# WimarcFarmArduinoShield.net
KiCad netlist of a schematic drawn in EAGLE
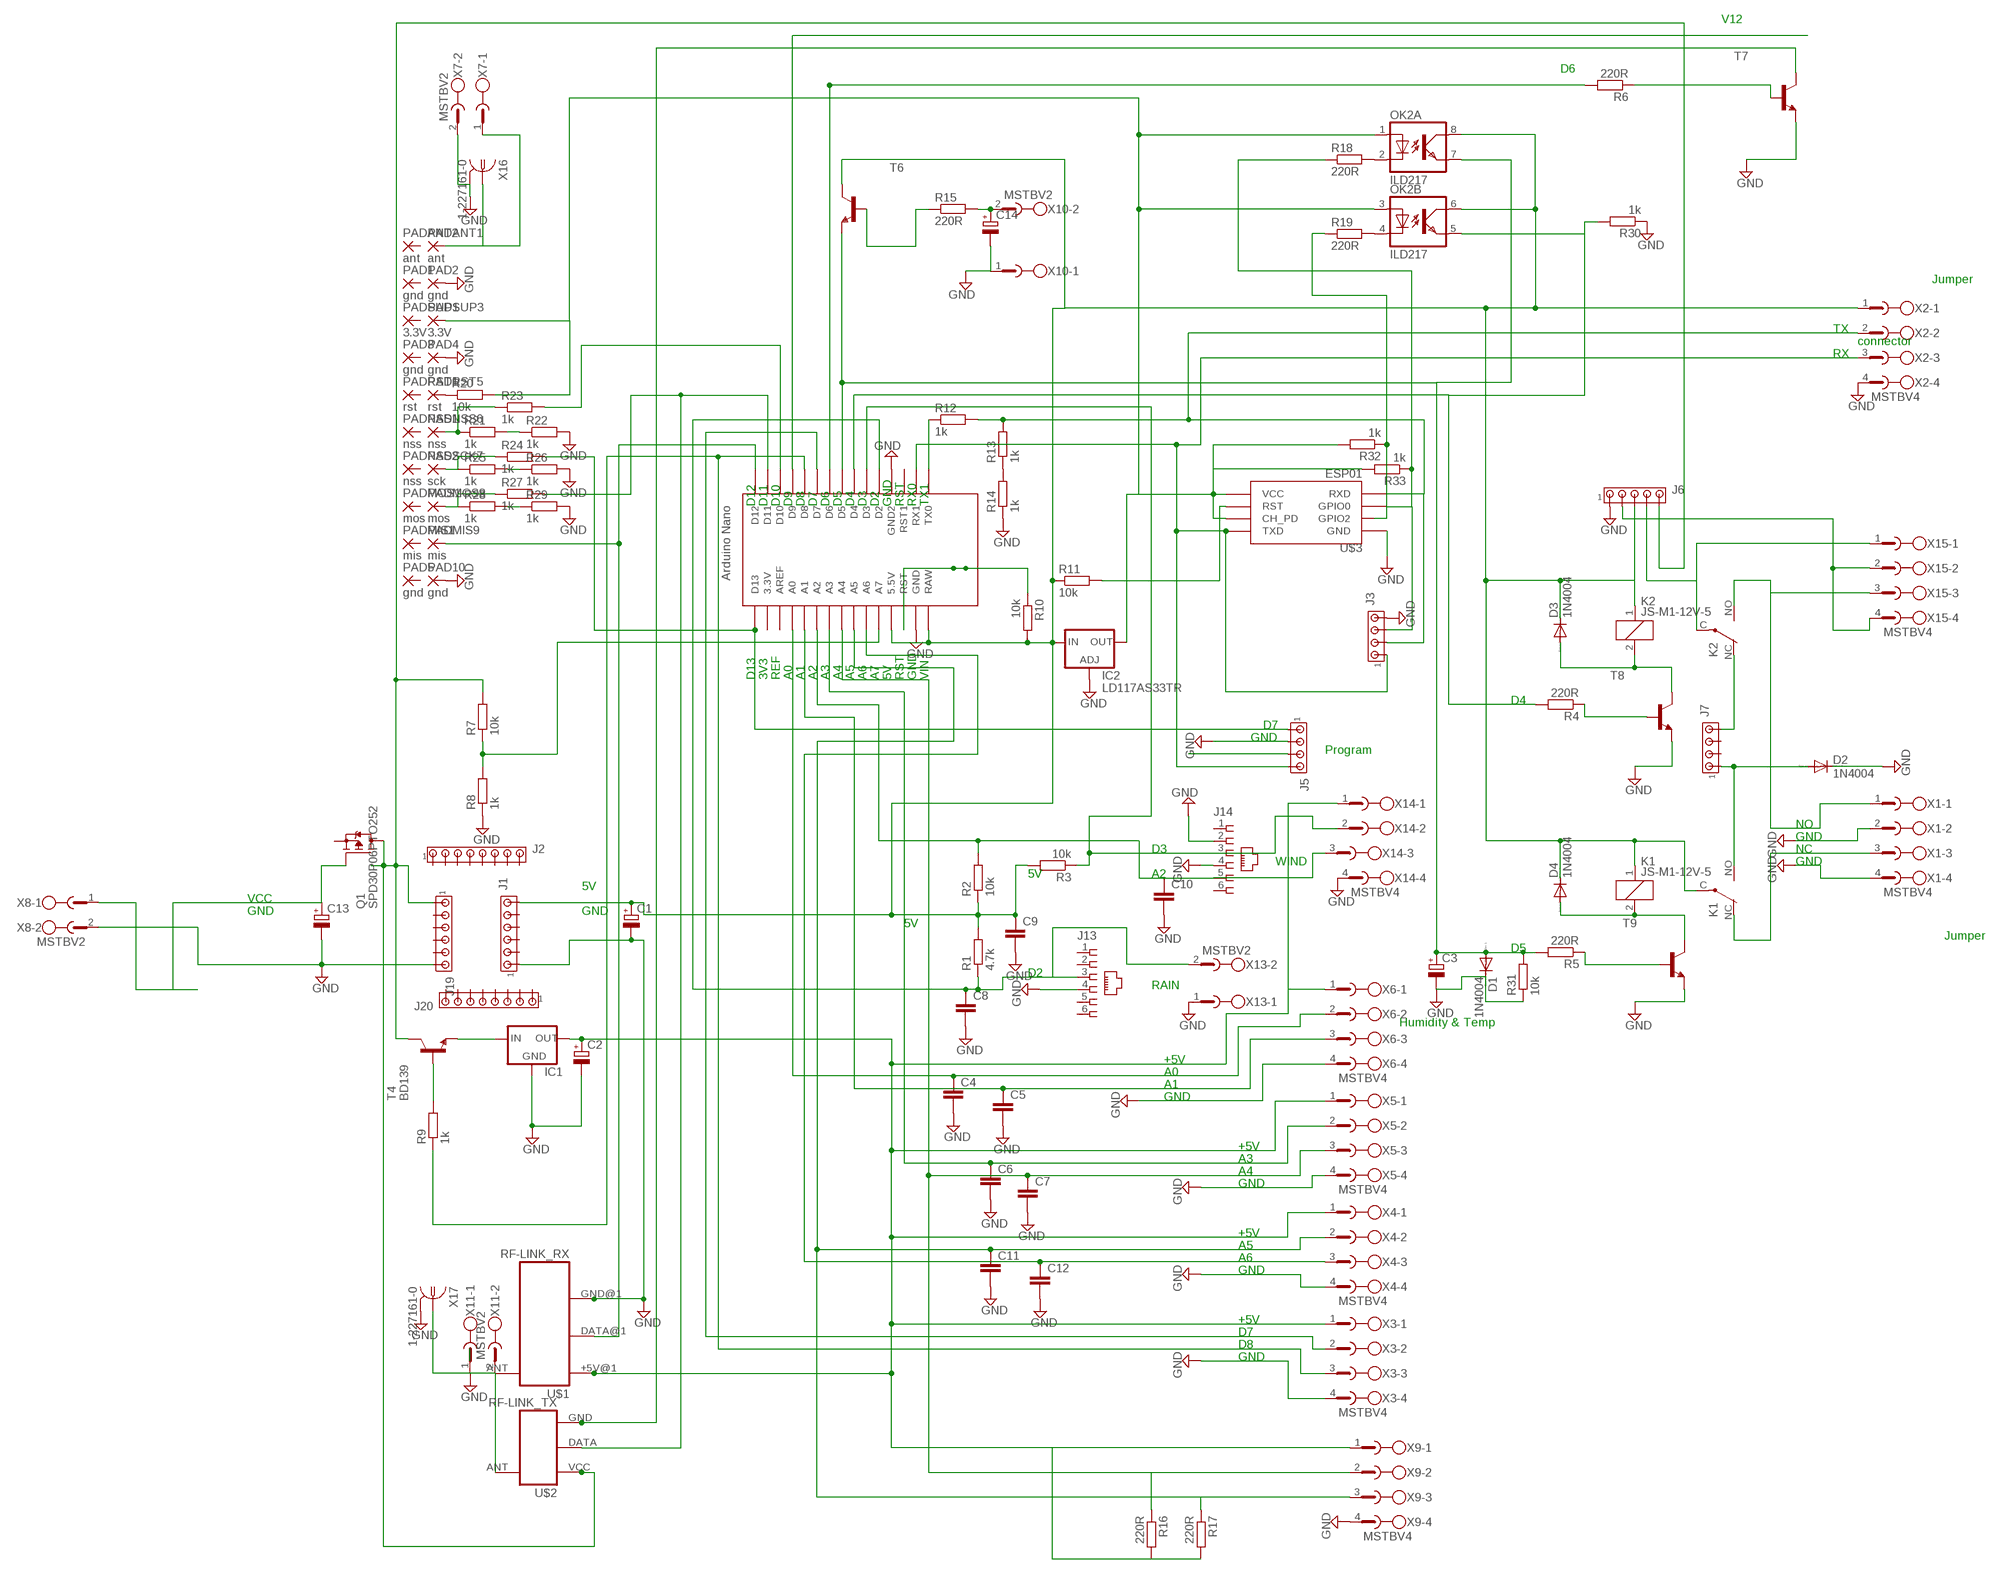
[diagram p0: schematic, sheet 1]

(export (version "E")
  (design (tool "Eeschema 10.0.6"))
  (components
    (comp (ref "C1")
      (value "CPOL-EUE2.5-7")
      (footprint "eagle-import:E2,5-7")
      (libsource (lib "eagle-import") (part "CPOL-EUE2.5-7"))
    )
    (comp (ref "C2")
      (value "CPOL-EUE3.5-10")
      (footprint "eagle-import:E3,5-10")
      (libsource (lib "eagle-import") (part "CPOL-EUE3.5-10"))
    )
    (comp (ref "C3")
      (value "CPOL-EUE2.5-7")
      (footprint "eagle-import:E2,5-7")
      (libsource (lib "eagle-import") (part "CPOL-EUE2.5-7"))
    )
    (comp (ref "C4")
      (value "C-EUC0805K")
      (footprint "eagle-import:C0805K")
      (libsource (lib "eagle-import") (part "C-EUC0805K"))
    )
    (comp (ref "C5")
      (value "C-EUC0805K")
      (footprint "eagle-import:C0805K")
      (libsource (lib "eagle-import") (part "C-EUC0805K"))
    )
    (comp (ref "C6")
      (value "C-EUC0805K")
      (footprint "eagle-import:C0805K")
      (libsource (lib "eagle-import") (part "C-EUC0805K"))
    )
    (comp (ref "C7")
      (value "C-EUC0805K")
      (footprint "eagle-import:C0805K")
      (libsource (lib "eagle-import") (part "C-EUC0805K"))
    )
    (comp (ref "C8")
      (value "C-EUC0805K")
      (footprint "eagle-import:C0805K")
      (libsource (lib "eagle-import") (part "C-EUC0805K"))
    )
    (comp (ref "C9")
      (value "C-EUC0805K")
      (footprint "eagle-import:C0805K")
      (libsource (lib "eagle-import") (part "C-EUC0805K"))
    )
    (comp (ref "C10")
      (value "C-EUC0805K")
      (footprint "eagle-import:C0805K")
      (libsource (lib "eagle-import") (part "C-EUC0805K"))
    )
    (comp (ref "C11")
      (value "C-EUC0805K")
      (footprint "eagle-import:C0805K")
      (libsource (lib "eagle-import") (part "C-EUC0805K"))
    )
    (comp (ref "C12")
      (value "C-EUC0805K")
      (footprint "eagle-import:C0805K")
      (libsource (lib "eagle-import") (part "C-EUC0805K"))
    )
    (comp (ref "C13")
      (value "CPOL-EUE2.5-7")
      (footprint "eagle-import:E2,5-7")
      (libsource (lib "eagle-import") (part "CPOL-EUE2.5-7"))
    )
    (comp (ref "C14")
      (value "CPOL-EUE2.5-7")
      (footprint "eagle-import:E2,5-7")
      (libsource (lib "eagle-import") (part "CPOL-EUE2.5-7"))
    )
    (comp (ref "D1")
      (value "1N4004")
      (footprint "eagle-import:DO41-10")
      (libsource (lib "eagle-import") (part "1N4004"))
    )
    (comp (ref "D2")
      (value "1N4004")
      (footprint "eagle-import:DO41-10")
      (libsource (lib "eagle-import") (part "1N4004"))
    )
    (comp (ref "D3")
      (value "1N4004")
      (footprint "eagle-import:DO41-10")
      (libsource (lib "eagle-import") (part "1N4004"))
    )
    (comp (ref "D4")
      (value "1N4004")
      (footprint "eagle-import:DO41-10")
      (libsource (lib "eagle-import") (part "1N4004"))
    )
    (comp (ref "IC1")
      (value "78XXS")
      (footprint "eagle-import:78XXS")
      (libsource (lib "eagle-import") (part "78XXS"))
    )
    (comp (ref "IC2")
      (value "LD117AS33TR")
      (footprint "eagle-import:SOT223")
      (libsource (lib "eagle-import") (part "LD117A?S33TR"))
    )
    (comp (ref "J1")
      (value "MTA06-100")
      (footprint "eagle-import:10X06MTA")
      (libsource (lib "eagle-import") (part "MTA06-100"))
    )
    (comp (ref "J2")
      (value "MTA08-100")
      (footprint "eagle-import:10X08MTA")
      (libsource (lib "eagle-import") (part "MTA08-100"))
    )
    (comp (ref "J3")
      (value "MTA04-100")
      (footprint "eagle-import:10X04MTA")
      (libsource (lib "eagle-import") (part "MTA04-100"))
    )
    (comp (ref "J5")
      (value "MTA04-100")
      (footprint "eagle-import:10X04MTA")
      (libsource (lib "eagle-import") (part "MTA04-100"))
    )
    (comp (ref "J6")
      (value "MTA05-100")
      (footprint "eagle-import:10X05MTA")
      (libsource (lib "eagle-import") (part "MTA05-100"))
    )
    (comp (ref "J7")
      (value "MTA04-100")
      (footprint "eagle-import:10X04MTA")
      (libsource (lib "eagle-import") (part "MTA04-100"))
    )
    (comp (ref "J13")
      (value "520250-3")
      (footprint "eagle-import:520250-3")
      (libsource (lib "eagle-import") (part "520250-3"))
    )
    (comp (ref "J14")
      (value "520250-3")
      (footprint "eagle-import:520250-3")
      (libsource (lib "eagle-import") (part "520250-3"))
    )
    (comp (ref "J19")
      (value "MTA06-100")
      (footprint "eagle-import:10X06MTA")
      (libsource (lib "eagle-import") (part "MTA06-100"))
    )
    (comp (ref "J20")
      (value "MTA08-100")
      (footprint "eagle-import:10X08MTA")
      (libsource (lib "eagle-import") (part "MTA08-100"))
    )
    (comp (ref "K1")
      (value "JS-M1-12V-5")
      (footprint "eagle-import:JS-M")
      (libsource (lib "eagle-import") (part "JS-M1-12V-5"))
    )
    (comp (ref "K2")
      (value "JS-M1-12V-5")
      (footprint "eagle-import:JS-M")
      (libsource (lib "eagle-import") (part "JS-M1-12V-5"))
    )
    (comp (ref "OK2")
      (value "ILD217")
      (footprint "eagle-import:SOIC08")
      (libsource (lib "eagle-import") (part "ILD217"))
    )
    (comp (ref "PAD1")
      (value "gnd")
      (footprint "eagle-import:1,6_0,8")
      (libsource (lib "eagle-import") (part "1,6/0,8"))
    )
    (comp (ref "PAD2")
      (value "gnd")
      (footprint "eagle-import:1,6_0,8")
      (libsource (lib "eagle-import") (part "1,6/0,8"))
    )
    (comp (ref "PAD3")
      (value "gnd")
      (footprint "eagle-import:1,6_0,8")
      (libsource (lib "eagle-import") (part "1,6/0,8"))
    )
    (comp (ref "PAD4")
      (value "gnd")
      (footprint "eagle-import:1,6_0,8")
      (libsource (lib "eagle-import") (part "1,6/0,8"))
    )
    (comp (ref "PAD5")
      (value "gnd")
      (footprint "eagle-import:1,6_0,8")
      (libsource (lib "eagle-import") (part "1,6/0,8"))
    )
    (comp (ref "PAD10")
      (value "gnd")
      (footprint "eagle-import:1,6_0,8")
      (libsource (lib "eagle-import") (part "1,6/0,8"))
    )
    (comp (ref "PADANT1")
      (value "ant")
      (footprint "eagle-import:1,6_0,8")
      (libsource (lib "eagle-import") (part "1,6/0,8"))
    )
    (comp (ref "PADANT2")
      (value "ant")
      (footprint "eagle-import:1,6_0,8")
      (libsource (lib "eagle-import") (part "1,6/0,8"))
    )
    (comp (ref "PADMIS1")
      (value "mis")
      (footprint "eagle-import:1,6_0,8")
      (libsource (lib "eagle-import") (part "1,6/0,8"))
    )
    (comp (ref "PADMIS9")
      (value "mis")
      (footprint "eagle-import:1,6_0,8")
      (libsource (lib "eagle-import") (part "1,6/0,8"))
    )
    (comp (ref "PADMOS1")
      (value "mos")
      (footprint "eagle-import:1,6_0,8")
      (libsource (lib "eagle-import") (part "1,6/0,8"))
    )
    (comp (ref "PADMOS8")
      (value "mos")
      (footprint "eagle-import:1,6_0,8")
      (libsource (lib "eagle-import") (part "1,6/0,8"))
    )
    (comp (ref "PADNSS1")
      (value "nss")
      (footprint "eagle-import:1,6_0,8")
      (libsource (lib "eagle-import") (part "1,6/0,8"))
    )
    (comp (ref "PADNSS2")
      (value "nss")
      (footprint "eagle-import:1,6_0,8")
      (libsource (lib "eagle-import") (part "1,6/0,8"))
    )
    (comp (ref "PADNSS6")
      (value "nss")
      (footprint "eagle-import:1,6_0,8")
      (libsource (lib "eagle-import") (part "1,6/0,8"))
    )
    (comp (ref "PADRST1")
      (value "rst")
      (footprint "eagle-import:1,6_0,8")
      (libsource (lib "eagle-import") (part "1,6/0,8"))
    )
    (comp (ref "PADRST5")
      (value "rst")
      (footprint "eagle-import:1,6_0,8")
      (libsource (lib "eagle-import") (part "1,6/0,8"))
    )
    (comp (ref "PADSCK7")
      (value "sck")
      (footprint "eagle-import:1,6_0,8")
      (libsource (lib "eagle-import") (part "1,6/0,8"))
    )
    (comp (ref "PADSUP1")
      (value "3.3V")
      (footprint "eagle-import:1,6_0,8")
      (libsource (lib "eagle-import") (part "1,6/0,8"))
    )
    (comp (ref "PADSUP3")
      (value "3.3V")
      (footprint "eagle-import:1,6_0,8")
      (libsource (lib "eagle-import") (part "1,6/0,8"))
    )
    (comp (ref "Q1")
      (value "SPD30P06PTO252")
      (footprint "eagle-import:TO252")
      (libsource (lib "eagle-import") (part "SPD30P06PTO252"))
    )
    (comp (ref "R1")
      (value "4.7k")
      (footprint "eagle-import:M0805")
      (libsource (lib "eagle-import") (part "R-EU_M0805"))
    )
    (comp (ref "R2")
      (value "10k")
      (footprint "eagle-import:M0805")
      (libsource (lib "eagle-import") (part "R-EU_M0805"))
    )
    (comp (ref "R3")
      (value "10k")
      (footprint "eagle-import:M0805")
      (libsource (lib "eagle-import") (part "R-EU_M0805"))
    )
    (comp (ref "R4")
      (value "220R")
      (footprint "eagle-import:M0805")
      (libsource (lib "eagle-import") (part "R-EU_M0805"))
    )
    (comp (ref "R5")
      (value "220R")
      (footprint "eagle-import:M0805")
      (libsource (lib "eagle-import") (part "R-EU_M0805"))
    )
    (comp (ref "R6")
      (value "220R")
      (footprint "eagle-import:M0805")
      (libsource (lib "eagle-import") (part "R-EU_M0805"))
    )
    (comp (ref "R7")
      (value "10k")
      (footprint "eagle-import:M0805")
      (libsource (lib "eagle-import") (part "R-EU_M0805"))
    )
    (comp (ref "R8")
      (value "1k")
      (footprint "eagle-import:M0805")
      (libsource (lib "eagle-import") (part "R-EU_M0805"))
    )
    (comp (ref "R9")
      (value "1k")
      (footprint "eagle-import:M0805")
      (libsource (lib "eagle-import") (part "R-EU_M0805"))
    )
    (comp (ref "R10")
      (value "10k")
      (footprint "eagle-import:M0805")
      (libsource (lib "eagle-import") (part "R-EU_M0805"))
    )
    (comp (ref "R11")
      (value "10k")
      (footprint "eagle-import:M0805")
      (libsource (lib "eagle-import") (part "R-EU_M0805"))
    )
    (comp (ref "R12")
      (value "1k")
      (footprint "eagle-import:M0805")
      (libsource (lib "eagle-import") (part "R-EU_M0805"))
    )
    (comp (ref "R13")
      (value "1k")
      (footprint "eagle-import:M0805")
      (libsource (lib "eagle-import") (part "R-EU_M0805"))
    )
    (comp (ref "R14")
      (value "1k")
      (footprint "eagle-import:M0805")
      (libsource (lib "eagle-import") (part "R-EU_M0805"))
    )
    (comp (ref "R15")
      (value "220R")
      (footprint "eagle-import:M0805")
      (libsource (lib "eagle-import") (part "R-EU_M0805"))
    )
    (comp (ref "R16")
      (value "220R")
      (footprint "eagle-import:M0805")
      (libsource (lib "eagle-import") (part "R-EU_M0805"))
    )
    (comp (ref "R17")
      (value "220R")
      (footprint "eagle-import:M0805")
      (libsource (lib "eagle-import") (part "R-EU_M0805"))
    )
    (comp (ref "R18")
      (value "220R")
      (footprint "eagle-import:M0805")
      (libsource (lib "eagle-import") (part "R-EU_M0805"))
    )
    (comp (ref "R19")
      (value "220R")
      (footprint "eagle-import:M0805")
      (libsource (lib "eagle-import") (part "R-EU_M0805"))
    )
    (comp (ref "R20")
      (value "10k")
      (footprint "eagle-import:M0805")
      (libsource (lib "eagle-import") (part "R-EU_M0805"))
    )
    (comp (ref "R21")
      (value "1k")
      (footprint "eagle-import:M0805")
      (libsource (lib "eagle-import") (part "R-EU_M0805"))
    )
    (comp (ref "R22")
      (value "1k")
      (footprint "eagle-import:M0805")
      (libsource (lib "eagle-import") (part "R-EU_M0805"))
    )
    (comp (ref "R23")
      (value "1k")
      (footprint "eagle-import:M0805")
      (libsource (lib "eagle-import") (part "R-EU_M0805"))
    )
    (comp (ref "R24")
      (value "1k")
      (footprint "eagle-import:M0805")
      (libsource (lib "eagle-import") (part "R-EU_M0805"))
    )
    (comp (ref "R25")
      (value "1k")
      (footprint "eagle-import:M0805")
      (libsource (lib "eagle-import") (part "R-EU_M0805"))
    )
    (comp (ref "R26")
      (value "1k")
      (footprint "eagle-import:M0805")
      (libsource (lib "eagle-import") (part "R-EU_M0805"))
    )
    (comp (ref "R27")
      (value "1k")
      (footprint "eagle-import:M0805")
      (libsource (lib "eagle-import") (part "R-EU_M0805"))
    )
    (comp (ref "R28")
      (value "1k")
      (footprint "eagle-import:M0805")
      (libsource (lib "eagle-import") (part "R-EU_M0805"))
    )
    (comp (ref "R29")
      (value "1k")
      (footprint "eagle-import:M0805")
      (libsource (lib "eagle-import") (part "R-EU_M0805"))
    )
    (comp (ref "R30")
      (value "1k")
      (footprint "eagle-import:M0805")
      (libsource (lib "eagle-import") (part "R-EU_M0805"))
    )
    (comp (ref "R31")
      (value "10k")
      (footprint "eagle-import:M0805")
      (libsource (lib "eagle-import") (part "R-EU_M0805"))
    )
    (comp (ref "R32")
      (value "1k")
      (footprint "eagle-import:M0805")
      (libsource (lib "eagle-import") (part "R-EU_M0805"))
    )
    (comp (ref "R33")
      (value "1k")
      (footprint "eagle-import:M0805")
      (libsource (lib "eagle-import") (part "R-EU_M0805"))
    )
    (comp (ref "T4")
      (value "BD139")
      (footprint "eagle-import:TO126")
      (libsource (lib "eagle-import") (part "BD139"))
    )
    (comp (ref "T6")
      (value "-NPN-SOT89-BCE")
      (footprint "eagle-import:SOT89-BCE")
      (libsource (lib "eagle-import") (part "-NPN-SOT89-BCE"))
    )
    (comp (ref "T7")
      (value "-NPN-SOT89-BCE")
      (footprint "eagle-import:SOT89-BCE")
      (libsource (lib "eagle-import") (part "-NPN-SOT89-BCE"))
    )
    (comp (ref "T8")
      (value "-NPN-SOT89-BCE")
      (footprint "eagle-import:SOT89-BCE")
      (libsource (lib "eagle-import") (part "-NPN-SOT89-BCE"))
    )
    (comp (ref "T9")
      (value "-NPN-SOT89-BCE")
      (footprint "eagle-import:SOT89-BCE")
      (libsource (lib "eagle-import") (part "-NPN-SOT89-BCE"))
    )
    (comp (ref "U$1")
      (value "RF-LINK_RX")
      (footprint "eagle-import:RF-LINK_RX")
      (libsource (lib "eagle-import") (part "RF-LINK_RX"))
    )
    (comp (ref "U$2")
      (value "RF-LINK_TX")
      (footprint "eagle-import:RF-LINK_TX")
      (libsource (lib "eagle-import") (part "RF-LINK_TX"))
    )
    (comp (ref "U$3")
      (value "ESP01")
      (footprint "eagle-import:ESP01")
      (libsource (lib "eagle-import") (part "ESP01"))
    )
    (comp (ref "U$4")
      (value "NANO")
      (footprint "eagle-import:NANO")
      (libsource (lib "eagle-import") (part "NANO"))
    )
    (comp (ref "X1")
      (value "MSTBV4")
      (footprint "eagle-import:MSTBV4")
      (libsource (lib "eagle-import") (part "MSTBV4"))
    )
    (comp (ref "X2")
      (value "MSTBV4")
      (footprint "eagle-import:MSTBV4")
      (libsource (lib "eagle-import") (part "MSTBV4"))
    )
    (comp (ref "X3")
      (value "MSTBV4")
      (footprint "eagle-import:MSTBV4")
      (libsource (lib "eagle-import") (part "MSTBV4"))
    )
    (comp (ref "X4")
      (value "MSTBV4")
      (footprint "eagle-import:MSTBV4")
      (libsource (lib "eagle-import") (part "MSTBV4"))
    )
    (comp (ref "X5")
      (value "MSTBV4")
      (footprint "eagle-import:MSTBV4")
      (libsource (lib "eagle-import") (part "MSTBV4"))
    )
    (comp (ref "X6")
      (value "MSTBV4")
      (footprint "eagle-import:MSTBV4")
      (libsource (lib "eagle-import") (part "MSTBV4"))
    )
    (comp (ref "X7")
      (value "MSTBV2")
      (footprint "eagle-import:MSTBV2")
      (libsource (lib "eagle-import") (part "MSTBV2"))
    )
    (comp (ref "X8")
      (value "MSTBV2")
      (footprint "eagle-import:MSTBV2")
      (libsource (lib "eagle-import") (part "MSTBV2"))
    )
    (comp (ref "X9")
      (value "MSTBV4")
      (footprint "eagle-import:MSTBV4")
      (libsource (lib "eagle-import") (part "MSTBV4"))
    )
    (comp (ref "X10")
      (value "MSTBV2")
      (footprint "eagle-import:MSTBV2")
      (libsource (lib "eagle-import") (part "MSTBV2"))
    )
    (comp (ref "X11")
      (value "MSTBV2")
      (footprint "eagle-import:MSTBV2")
      (libsource (lib "eagle-import") (part "MSTBV2"))
    )
    (comp (ref "X13")
      (value "MSTBV2")
      (footprint "eagle-import:MSTBV2")
      (libsource (lib "eagle-import") (part "MSTBV2"))
    )
    (comp (ref "X14")
      (value "MSTBV4")
      (footprint "eagle-import:MSTBV4")
      (libsource (lib "eagle-import") (part "MSTBV4"))
    )
    (comp (ref "X15")
      (value "MSTBV4")
      (footprint "eagle-import:MSTBV4")
      (libsource (lib "eagle-import") (part "MSTBV4"))
    )
    (comp (ref "X16")
      (value "1-227161-0")
      (footprint "eagle-import:AMP_227161")
      (fields (field (name "MF") "TYCO ELECTRONICS") (field (name "MPN") "1-227161"))
      (libsource (lib "eagle-import") (part "?2271611--0"))
    )
    (comp (ref "X17")
      (value "1-227161-0")
      (footprint "eagle-import:AMP_227161")
      (fields (field (name "MF") "TYCO ELECTRONICS") (field (name "MPN") "1-227161"))
      (libsource (lib "eagle-import") (part "?2271611--0"))
    )
  )
  (nets
    (net (code "1") (name "GND") (class "Default")
      (node (ref "C1") (pin "-") (pinfunction "-_-") (pintype "passive"))
      (node (ref "C10") (pin "2") (pinfunction "2_2") (pintype "passive"))
      (node (ref "C11") (pin "2") (pinfunction "2_2") (pintype "passive"))
      (node (ref "C12") (pin "2") (pinfunction "2_2") (pintype "passive"))
      (node (ref "C13") (pin "-") (pinfunction "-_-") (pintype "passive"))
      (node (ref "C14") (pin "-") (pinfunction "-_-") (pintype "passive"))
      (node (ref "C2") (pin "-") (pinfunction "-_-") (pintype "passive"))
      (node (ref "C3") (pin "-") (pinfunction "-_-") (pintype "passive"))
      (node (ref "C4") (pin "2") (pinfunction "2_2") (pintype "passive"))
      (node (ref "C5") (pin "2") (pinfunction "2_2") (pintype "passive"))
      (node (ref "C6") (pin "2") (pinfunction "2_2") (pintype "passive"))
      (node (ref "C7") (pin "2") (pinfunction "2_2") (pintype "passive"))
      (node (ref "C8") (pin "2") (pinfunction "2_2") (pintype "passive"))
      (node (ref "C9") (pin "2") (pinfunction "2_2") (pintype "passive"))
      (node (ref "D1") (pin "C") (pinfunction "C_C") (pintype "passive"))
      (node (ref "D2") (pin "C") (pinfunction "C_C") (pintype "passive"))
      (node (ref "IC1") (pin "GND") (pinfunction "GND_GND") (pintype "input"))
      (node (ref "IC2") (pin "1") (pinfunction "ADJ_1") (pintype "input"))
      (node (ref "J1") (pin "1") (pinfunction "1_1") (pintype "passive"))
      (node (ref "J13") (pin "4") (pinfunction "4_4") (pintype "passive"))
      (node (ref "J14") (pin "2") (pinfunction "2_2") (pintype "passive"))
      (node (ref "J14") (pin "4") (pinfunction "4_4") (pintype "passive"))
      (node (ref "J19") (pin "6") (pinfunction "6_6") (pintype "passive"))
      (node (ref "J3") (pin "4") (pinfunction "4_4") (pintype "passive"))
      (node (ref "J5") (pin "2") (pinfunction "2_2") (pintype "passive"))
      (node (ref "J6") (pin "1") (pinfunction "1_1") (pintype "passive"))
      (node (ref "PAD10") (pin "1") (pinfunction "P_1") (pintype "passive"))
      (node (ref "PAD2") (pin "1") (pinfunction "P_1") (pintype "passive"))
      (node (ref "PAD4") (pin "1") (pinfunction "P_1") (pintype "passive"))
      (node (ref "R14") (pin "1") (pinfunction "1_1") (pintype "passive"))
      (node (ref "R22") (pin "2") (pinfunction "2_2") (pintype "passive"))
      (node (ref "R26") (pin "2") (pinfunction "2_2") (pintype "passive"))
      (node (ref "R29") (pin "2") (pinfunction "2_2") (pintype "passive"))
      (node (ref "R30") (pin "1") (pinfunction "1_1") (pintype "passive"))
      (node (ref "R31") (pin "1") (pinfunction "1_1") (pintype "passive"))
      (node (ref "R8") (pin "1") (pinfunction "1_1") (pintype "passive"))
      (node (ref "T7") (pin "E") (pinfunction "E_E") (pintype "passive"))
      (node (ref "T8") (pin "E") (pinfunction "E_E") (pintype "passive"))
      (node (ref "T9") (pin "E") (pinfunction "E_E") (pintype "passive"))
      (node (ref "U$1") (pin "GND@1") (pinfunction "GND_GND@1") (pintype "power_in"))
      (node (ref "U$3") (pin "GND") (pinfunction "GND_GND") (pintype "bidirectional"))
      (node (ref "U$4") (pin "GND") (pinfunction "GND_GND") (pintype "bidirectional"))
      (node (ref "U$4") (pin "GND1") (pinfunction "GND2_GND1") (pintype "bidirectional"))
      (node (ref "X1") (pin "2") (pinfunction "1_2") (pintype "passive"))
      (node (ref "X1") (pin "4") (pinfunction "1_4") (pintype "passive"))
      (node (ref "X10") (pin "1") (pinfunction "1_1") (pintype "passive"))
      (node (ref "X11") (pin "1") (pinfunction "1_1") (pintype "passive"))
      (node (ref "X13") (pin "1") (pinfunction "1_1") (pintype "passive"))
      (node (ref "X14") (pin "4") (pinfunction "1_4") (pintype "passive"))
      (node (ref "X16") (pin "2") (pinfunction "2_2") (pintype "passive"))
      (node (ref "X17") (pin "2") (pinfunction "2_2") (pintype "passive"))
      (node (ref "X2") (pin "4") (pinfunction "1_4") (pintype "passive"))
      (node (ref "X3") (pin "4") (pinfunction "1_4") (pintype "passive"))
      (node (ref "X4") (pin "4") (pinfunction "1_4") (pintype "passive"))
      (node (ref "X5") (pin "4") (pinfunction "1_4") (pintype "passive"))
      (node (ref "X6") (pin "4") (pinfunction "1_4") (pintype "passive"))
      (node (ref "X7") (pin "2") (pinfunction "1_2") (pintype "passive"))
      (node (ref "X8") (pin "2") (pinfunction "1_2") (pintype "passive"))
      (node (ref "X9") (pin "4") (pinfunction "1_4") (pintype "passive"))
    )
    (net (code "2") (name "Net-(D3-PadA)") (class "Default")
      (node (ref "D3") (pin "A") (pinfunction "A_A") (pintype "passive"))
      (node (ref "K2") (pin "2") (pinfunction "2_2") (pintype "passive"))
      (node (ref "T8") (pin "C") (pinfunction "C_C") (pintype "passive"))
    )
    (net (code "3") (name "Net-(D4-PadA)") (class "Default")
      (node (ref "D4") (pin "A") (pinfunction "A_A") (pintype "passive"))
      (node (ref "K1") (pin "2") (pinfunction "2_2") (pintype "passive"))
      (node (ref "T9") (pin "C") (pinfunction "C_C") (pintype "passive"))
    )
    (net (code "4") (name "Net-(IC2-IN)") (class "Default")
      (node (ref "C1") (pin "+") (pinfunction "+_+") (pintype "passive"))
      (node (ref "C9") (pin "1") (pinfunction "1_1") (pintype "passive"))
      (node (ref "D3") (pin "C") (pinfunction "C_C") (pintype "passive"))
      (node (ref "D4") (pin "C") (pinfunction "C_C") (pintype "passive"))
      (node (ref "IC2") (pin "3") (pinfunction "IN_3") (pintype "input"))
      (node (ref "J1") (pin "6") (pinfunction "6_6") (pintype "passive"))
      (node (ref "J6") (pin "3") (pinfunction "3_3") (pintype "passive"))
      (node (ref "K1") (pin "1") (pinfunction "1_1") (pintype "passive"))
      (node (ref "K1") (pin "C") (pinfunction "P_C") (pintype "passive"))
      (node (ref "K2") (pin "1") (pinfunction "1_1") (pintype "passive"))
      (node (ref "OK2") (pin "6") (pinfunction "COL_6") (pintype "passive"))
      (node (ref "OK2") (pin "8") (pinfunction "COL_8") (pintype "passive"))
      (node (ref "R1") (pin "2") (pinfunction "2_2") (pintype "passive"))
      (node (ref "R10") (pin "2") (pinfunction "2_2") (pintype "passive"))
      (node (ref "R11") (pin "1") (pinfunction "1_1") (pintype "passive"))
      (node (ref "R2") (pin "1") (pinfunction "1_1") (pintype "passive"))
      (node (ref "R3") (pin "2") (pinfunction "2_2") (pintype "passive"))
      (node (ref "T6") (pin "C") (pinfunction "C_C") (pintype "passive"))
      (node (ref "U$4") (pin "5V") (pinfunction "5.5V_5V") (pintype "bidirectional"))
      (node (ref "U$4") (pin "RAW") (pinfunction "RAW_RAW") (pintype "bidirectional"))
      (node (ref "X2") (pin "1") (pinfunction "1_1") (pintype "passive"))
    )
    (net (code "5") (name "Net-(IC2-OUT)") (class "Default")
      (node (ref "IC2") (pin "4") (pinfunction "OUT_4") (pintype "passive"))
      (node (ref "OK2") (pin "1") (pinfunction "A_1") (pintype "passive"))
      (node (ref "OK2") (pin "3") (pinfunction "A_3") (pintype "passive"))
      (node (ref "PADSUP3") (pin "1") (pinfunction "P_1") (pintype "passive"))
      (node (ref "R20") (pin "2") (pinfunction "2_2") (pintype "passive"))
      (node (ref "R32") (pin "2") (pinfunction "2_2") (pintype "passive"))
      (node (ref "R33") (pin "2") (pinfunction "2_2") (pintype "passive"))
      (node (ref "U$3") (pin "CH_PD") (pinfunction "CH_PD_CH_PD") (pintype "bidirectional"))
      (node (ref "U$3") (pin "VCC") (pinfunction "VCC_VCC") (pintype "bidirectional"))
    )
    (net (code "6") (name "Net-(J3-Pad3)") (class "Default")
      (node (ref "J3") (pin "3") (pinfunction "3_3") (pintype "passive"))
      (node (ref "R18") (pin "1") (pinfunction "1_1") (pintype "passive"))
      (node (ref "R33") (pin "1") (pinfunction "1_1") (pintype "passive"))
      (node (ref "U$3") (pin "GPIO0") (pinfunction "GPIO0_GPIO0") (pintype "bidirectional"))
    )
    (net (code "7") (name "Net-(J5-Pad1)") (class "Default")
      (node (ref "J5") (pin "1") (pinfunction "1_1") (pintype "passive"))
      (node (ref "R24") (pin "2") (pinfunction "2_2") (pintype "passive"))
      (node (ref "U$4") (pin "D13") (pinfunction "D13_D13") (pintype "bidirectional"))
    )
    (net (code "8") (name "Net-(K1B-O)") (class "Default")
      (node (ref "K1") (pin "NC") (pinfunction "O_NC") (pintype "passive"))
      (node (ref "X1") (pin "3") (pinfunction "1_3") (pintype "passive"))
    )
    (net (code "9") (name "Net-(K1B-S)") (class "Default")
      (node (ref "D2") (pin "A") (pinfunction "A_A") (pintype "passive"))
      (node (ref "J7") (pin "1") (pinfunction "1_1") (pintype "passive"))
      (node (ref "K1") (pin "NO") (pinfunction "S_NO") (pintype "passive"))
    )
    (net (code "10") (name "Net-(K2B-O)") (class "Default")
      (node (ref "J7") (pin "4") (pinfunction "4_4") (pintype "passive"))
      (node (ref "K2") (pin "NC") (pinfunction "O_NC") (pintype "passive"))
    )
    (net (code "11") (name "Net-(K2B-P)") (class "Default")
      (node (ref "J6") (pin "4") (pinfunction "4_4") (pintype "passive"))
      (node (ref "K2") (pin "C") (pinfunction "P_C") (pintype "passive"))
      (node (ref "X15") (pin "1") (pinfunction "1_1") (pintype "passive"))
    )
    (net (code "12") (name "Net-(K2B-S)") (class "Default")
      (node (ref "K2") (pin "NO") (pinfunction "S_NO") (pintype "passive"))
      (node (ref "X1") (pin "1") (pinfunction "1_1") (pintype "passive"))
      (node (ref "X15") (pin "3") (pinfunction "1_3") (pintype "passive"))
    )
    (net (code "13") (name "Net-(OK2A-C)") (class "Default")
      (node (ref "OK2") (pin "2") (pinfunction "C_2") (pintype "passive"))
      (node (ref "R18") (pin "2") (pinfunction "2_2") (pintype "passive"))
    )
    (net (code "14") (name "Net-(OK2A-EMIT)") (class "Default")
      (node (ref "C3") (pin "+") (pinfunction "+_+") (pintype "passive"))
      (node (ref "D1") (pin "A") (pinfunction "A_A") (pintype "passive"))
      (node (ref "OK2") (pin "7") (pinfunction "EMIT_7") (pintype "passive"))
      (node (ref "R31") (pin "2") (pinfunction "2_2") (pintype "passive"))
      (node (ref "R5") (pin "2") (pinfunction "2_2") (pintype "passive"))
      (node (ref "T6") (pin "E") (pinfunction "E_E") (pintype "passive"))
      (node (ref "U$4") (pin "D5") (pinfunction "D5_D5") (pintype "bidirectional"))
    )
    (net (code "15") (name "Net-(OK2B-C)") (class "Default")
      (node (ref "OK2") (pin "4") (pinfunction "C_4") (pintype "passive"))
      (node (ref "R19") (pin "2") (pinfunction "2_2") (pintype "passive"))
    )
    (net (code "16") (name "Net-(OK2B-EMIT)") (class "Default")
      (node (ref "OK2") (pin "5") (pinfunction "EMIT_5") (pintype "passive"))
      (node (ref "R30") (pin "2") (pinfunction "2_2") (pintype "passive"))
      (node (ref "R4") (pin "2") (pinfunction "2_2") (pintype "passive"))
      (node (ref "U$4") (pin "D4") (pinfunction "D4_D4") (pintype "bidirectional"))
    )
    (net (code "17") (name "Net-(PADANT1-P)") (class "Default")
      (node (ref "PADANT1") (pin "1") (pinfunction "P_1") (pintype "passive"))
      (node (ref "X16") (pin "1") (pinfunction "1_1") (pintype "passive"))
      (node (ref "X7") (pin "1") (pinfunction "1_1") (pintype "passive"))
    )
    (net (code "18") (name "Net-(PADMIS9-P)") (class "Default")
      (node (ref "PADMIS9") (pin "1") (pinfunction "P_1") (pintype "passive"))
      (node (ref "U$1") (pin "DATA@1") (pinfunction "DATA_DATA@1") (pintype "input"))
      (node (ref "U$4") (pin "D12") (pinfunction "D12_D12") (pintype "bidirectional"))
    )
    (net (code "19") (name "Net-(PADMOS8-P)") (class "Default")
      (node (ref "PADMOS8") (pin "1") (pinfunction "P_1") (pintype "passive"))
      (node (ref "R27") (pin "1") (pinfunction "1_1") (pintype "passive"))
      (node (ref "R28") (pin "1") (pinfunction "1_1") (pintype "passive"))
    )
    (net (code "20") (name "Net-(PADNSS6-P)") (class "Default")
      (node (ref "PADNSS6") (pin "1") (pinfunction "P_1") (pintype "passive"))
      (node (ref "R21") (pin "1") (pinfunction "1_1") (pintype "passive"))
      (node (ref "R23") (pin "1") (pinfunction "1_1") (pintype "passive"))
    )
    (net (code "21") (name "Net-(PADRST5-P)") (class "Default")
      (node (ref "PADRST5") (pin "1") (pinfunction "P_1") (pintype "passive"))
      (node (ref "R20") (pin "1") (pinfunction "1_1") (pintype "passive"))
    )
    (net (code "22") (name "Net-(PADSCK7-P)") (class "Default")
      (node (ref "PADSCK7") (pin "1") (pinfunction "P_1") (pintype "passive"))
      (node (ref "R24") (pin "1") (pinfunction "1_1") (pintype "passive"))
      (node (ref "R25") (pin "1") (pinfunction "1_1") (pintype "passive"))
    )
    (net (code "23") (name "Net-(Q1-D)") (class "Default")
      (node (ref "J19") (pin "1") (pinfunction "1_1") (pintype "passive"))
      (node (ref "J6") (pin "5") (pinfunction "5_5") (pintype "passive"))
      (node (ref "Q1") (pin "3") (pinfunction "D_3") (pintype "passive"))
      (node (ref "R7") (pin "2") (pinfunction "2_2") (pintype "passive"))
      (node (ref "T4") (pin "2") (pinfunction "C_2") (pintype "passive"))
      (node (ref "U$2") (pin "VCC") (pinfunction "+5V_VCC") (pintype "power_in"))
    )
    (net (code "24") (name "Net-(Q1-G)") (class "Default")
      (node (ref "C13") (pin "+") (pinfunction "+_+") (pintype "passive"))
      (node (ref "Q1") (pin "1") (pinfunction "G_1") (pintype "passive"))
      (node (ref "X8") (pin "1") (pinfunction "1_1") (pintype "passive"))
    )
    (net (code "25") (name "Net-(R4-Pad1)") (class "Default")
      (node (ref "R4") (pin "1") (pinfunction "1_1") (pintype "passive"))
      (node (ref "T8") (pin "B") (pinfunction "B_B") (pintype "passive"))
    )
    (net (code "26") (name "Net-(R5-Pad1)") (class "Default")
      (node (ref "R5") (pin "1") (pinfunction "1_1") (pintype "passive"))
      (node (ref "T9") (pin "B") (pinfunction "B_B") (pintype "passive"))
    )
    (net (code "27") (name "Net-(R6-Pad1)") (class "Default")
      (node (ref "R6") (pin "1") (pinfunction "1_1") (pintype "passive"))
      (node (ref "T7") (pin "B") (pinfunction "B_B") (pintype "passive"))
    )
    (net (code "28") (name "Net-(R6-Pad2)") (class "Default")
      (node (ref "R6") (pin "2") (pinfunction "2_2") (pintype "passive"))
      (node (ref "U$4") (pin "D6") (pinfunction "D6_D6") (pintype "bidirectional"))
    )
    (net (code "29") (name "Net-(R7-Pad1)") (class "Default")
      (node (ref "R7") (pin "1") (pinfunction "1_1") (pintype "passive"))
      (node (ref "R8") (pin "2") (pinfunction "2_2") (pintype "passive"))
      (node (ref "U$4") (pin "A7") (pinfunction "A7_A7") (pintype "bidirectional"))
    )
    (net (code "30") (name "Net-(R10-Pad1)") (class "Default")
      (node (ref "R10") (pin "1") (pinfunction "1_1") (pintype "passive"))
      (node (ref "U$4") (pin "ICSP1") (pinfunction "ICSP1_ICSP1") (pintype "bidirectional"))
      (node (ref "U$4") (pin "ICSP2") (pinfunction "ICSP2_ICSP2") (pintype "bidirectional"))
      (node (ref "U$4") (pin "RST") (pinfunction "RST_RST") (pintype "bidirectional"))
    )
    (net (code "31") (name "Net-(R11-Pad2)") (class "Default")
      (node (ref "R11") (pin "2") (pinfunction "2_2") (pintype "passive"))
      (node (ref "U$3") (pin "RST") (pinfunction "RST_RST") (pintype "bidirectional"))
    )
    (net (code "32") (name "Net-(R12-Pad1)") (class "Default")
      (node (ref "R12") (pin "1") (pinfunction "1_1") (pintype "passive"))
      (node (ref "U$4") (pin "TX0") (pinfunction "TX0_TX0") (pintype "bidirectional"))
    )
    (net (code "33") (name "Net-(R13-Pad1)") (class "Default")
      (node (ref "R13") (pin "1") (pinfunction "1_1") (pintype "passive"))
      (node (ref "R14") (pin "2") (pinfunction "2_2") (pintype "passive"))
    )
    (net (code "34") (name "Net-(R15-Pad1)") (class "Default")
      (node (ref "R15") (pin "1") (pinfunction "1_1") (pintype "passive"))
      (node (ref "T6") (pin "B") (pinfunction "B_B") (pintype "passive"))
    )
    (net (code "35") (name "Net-(R19-Pad1)") (class "Default")
      (node (ref "R19") (pin "1") (pinfunction "1_1") (pintype "passive"))
      (node (ref "R32") (pin "1") (pinfunction "1_1") (pintype "passive"))
      (node (ref "U$3") (pin "GPIO2") (pinfunction "GPIO2_GPIO2") (pintype "bidirectional"))
    )
    (net (code "36") (name "Net-(R21-Pad2)") (class "Default")
      (node (ref "R21") (pin "2") (pinfunction "2_2") (pintype "passive"))
      (node (ref "R22") (pin "1") (pinfunction "1_1") (pintype "passive"))
    )
    (net (code "37") (name "Net-(R23-Pad2)") (class "Default")
      (node (ref "R23") (pin "2") (pinfunction "2_2") (pintype "passive"))
      (node (ref "U$4") (pin "D10") (pinfunction "D10_D10") (pintype "bidirectional"))
    )
    (net (code "38") (name "Net-(R25-Pad2)") (class "Default")
      (node (ref "R25") (pin "2") (pinfunction "2_2") (pintype "passive"))
      (node (ref "R26") (pin "1") (pinfunction "1_1") (pintype "passive"))
    )
    (net (code "39") (name "Net-(R27-Pad2)") (class "Default")
      (node (ref "R27") (pin "2") (pinfunction "2_2") (pintype "passive"))
      (node (ref "U$2") (pin "DATA") (pinfunction "DATA_DATA") (pintype "input"))
      (node (ref "U$4") (pin "D11") (pinfunction "D11_D11") (pintype "bidirectional"))
    )
    (net (code "40") (name "Net-(R28-Pad2)") (class "Default")
      (node (ref "R28") (pin "2") (pinfunction "2_2") (pintype "passive"))
      (node (ref "R29") (pin "1") (pinfunction "1_1") (pintype "passive"))
    )
    (net (code "41") (name "Net-(T4-B)") (class "Default")
      (node (ref "R9") (pin "2") (pinfunction "2_2") (pintype "passive"))
      (node (ref "T4") (pin "3") (pinfunction "B_3") (pintype "passive"))
    )
    (net (code "42") (name "Net-(T4-E)") (class "Default")
      (node (ref "IC1") (pin "IN") (pinfunction "IN_IN") (pintype "input"))
      (node (ref "T4") (pin "1") (pinfunction "E_1") (pintype "passive"))
    )
    (net (code "43") (name "Net-(T7-PadC)") (class "Default")
      (node (ref "T7") (pin "C") (pinfunction "C_C") (pintype "passive"))
      (node (ref "U$2") (pin "GND") (pinfunction "GND_GND") (pintype "power_in"))
    )
    (net (code "44") (name "Net-(U$1-+5V)") (class "Default")
      (node (ref "C2") (pin "+") (pinfunction "+_+") (pintype "passive"))
      (node (ref "IC1") (pin "OUT") (pinfunction "OUT_OUT") (pintype "passive"))
      (node (ref "R16") (pin "2") (pinfunction "2_2") (pintype "passive"))
      (node (ref "R17") (pin "2") (pinfunction "2_2") (pintype "passive"))
      (node (ref "U$1") (pin "+5V@1") (pinfunction "+5V_+5V@1") (pintype "power_in"))
      (node (ref "X14") (pin "1") (pinfunction "1_1") (pintype "passive"))
      (node (ref "X3") (pin "1") (pinfunction "1_1") (pintype "passive"))
      (node (ref "X4") (pin "1") (pinfunction "1_1") (pintype "passive"))
      (node (ref "X5") (pin "1") (pinfunction "1_1") (pintype "passive"))
      (node (ref "X6") (pin "1") (pinfunction "1_1") (pintype "passive"))
      (node (ref "X9") (pin "1") (pinfunction "1_1") (pintype "passive"))
    )
    (net (code "45") (name "Net-(U$3-RXD)") (class "Default")
      (node (ref "J3") (pin "2") (pinfunction "2_2") (pintype "passive"))
      (node (ref "R12") (pin "2") (pinfunction "2_2") (pintype "passive"))
      (node (ref "R13") (pin "2") (pinfunction "2_2") (pintype "passive"))
      (node (ref "U$3") (pin "RX") (pinfunction "RXD_RX") (pintype "bidirectional"))
      (node (ref "X2") (pin "2") (pinfunction "1_2") (pintype "passive"))
    )
    (net (code "46") (name "Net-(U$3-TXD)") (class "Default")
      (node (ref "J3") (pin "1") (pinfunction "1_1") (pintype "passive"))
      (node (ref "J5") (pin "4") (pinfunction "4_4") (pintype "passive"))
      (node (ref "U$3") (pin "TX") (pinfunction "TXD_TX") (pintype "bidirectional"))
      (node (ref "U$4") (pin "RX1") (pinfunction "RX1_RX1") (pintype "bidirectional"))
      (node (ref "X2") (pin "3") (pinfunction "1_3") (pintype "passive"))
    )
    (net (code "47") (name "Net-(X3B-1)") (class "Default")
      (node (ref "U$4") (pin "D7") (pinfunction "D7_D7") (pintype "bidirectional"))
      (node (ref "X3") (pin "2") (pinfunction "1_2") (pintype "passive"))
    )
    (net (code "48") (name "Net-(X3C-1)") (class "Default")
      (node (ref "R9") (pin "1") (pinfunction "1_1") (pintype "passive"))
      (node (ref "U$4") (pin "D8") (pinfunction "D8_D8") (pintype "bidirectional"))
      (node (ref "X3") (pin "3") (pinfunction "1_3") (pintype "passive"))
    )
    (net (code "49") (name "Net-(X4B-1)") (class "Default")
      (node (ref "C11") (pin "1") (pinfunction "1_1") (pintype "passive"))
      (node (ref "R17") (pin "1") (pinfunction "1_1") (pintype "passive"))
      (node (ref "U$4") (pin "A5") (pinfunction "A5_A5") (pintype "bidirectional"))
      (node (ref "X4") (pin "2") (pinfunction "1_2") (pintype "passive"))
      (node (ref "X9") (pin "3") (pinfunction "1_3") (pintype "passive"))
    )
    (net (code "50") (name "Net-(X4C-1)") (class "Default")
      (node (ref "C12") (pin "1") (pinfunction "1_1") (pintype "passive"))
      (node (ref "U$4") (pin "A6") (pinfunction "A6_A6") (pintype "bidirectional"))
      (node (ref "X4") (pin "3") (pinfunction "1_3") (pintype "passive"))
    )
    (net (code "51") (name "Net-(X5B-1)") (class "Default")
      (node (ref "C6") (pin "1") (pinfunction "1_1") (pintype "passive"))
      (node (ref "U$4") (pin "A3") (pinfunction "A3_A3") (pintype "bidirectional"))
      (node (ref "X5") (pin "2") (pinfunction "1_2") (pintype "passive"))
    )
    (net (code "52") (name "Net-(X5C-1)") (class "Default")
      (node (ref "C7") (pin "1") (pinfunction "1_1") (pintype "passive"))
      (node (ref "R16") (pin "1") (pinfunction "1_1") (pintype "passive"))
      (node (ref "U$4") (pin "A4") (pinfunction "A4_A4") (pintype "bidirectional"))
      (node (ref "X5") (pin "3") (pinfunction "1_3") (pintype "passive"))
      (node (ref "X9") (pin "2") (pinfunction "1_2") (pintype "passive"))
    )
    (net (code "53") (name "Net-(X6B-1)") (class "Default")
      (node (ref "C4") (pin "1") (pinfunction "1_1") (pintype "passive"))
      (node (ref "U$4") (pin "A0") (pinfunction "A0_A0") (pintype "bidirectional"))
      (node (ref "X6") (pin "2") (pinfunction "1_2") (pintype "passive"))
    )
    (net (code "54") (name "Net-(X6C-1)") (class "Default")
      (node (ref "C5") (pin "1") (pinfunction "1_1") (pintype "passive"))
      (node (ref "U$4") (pin "A1") (pinfunction "A1_A1") (pintype "bidirectional"))
      (node (ref "X6") (pin "3") (pinfunction "1_3") (pintype "passive"))
    )
    (net (code "55") (name "Net-(X10B-1)") (class "Default")
      (node (ref "C14") (pin "+") (pinfunction "+_+") (pintype "passive"))
      (node (ref "R15") (pin "2") (pinfunction "2_2") (pintype "passive"))
      (node (ref "X10") (pin "2") (pinfunction "1_2") (pintype "passive"))
    )
    (net (code "56") (name "Net-(X11B-1)") (class "Default")
      (node (ref "U$1") (pin "ANT") (pinfunction "ANT_ANT") (pintype "passive"))
      (node (ref "U$2") (pin "ANT") (pinfunction "ANT_ANT") (pintype "passive"))
      (node (ref "X11") (pin "2") (pinfunction "1_2") (pintype "passive"))
      (node (ref "X17") (pin "1") (pinfunction "1_1") (pintype "passive"))
    )
    (net (code "57") (name "Net-(X13B-1)") (class "Default")
      (node (ref "C8") (pin "1") (pinfunction "1_1") (pintype "passive"))
      (node (ref "J13") (pin "3") (pinfunction "3_3") (pintype "passive"))
      (node (ref "R1") (pin "1") (pinfunction "1_1") (pintype "passive"))
      (node (ref "U$4") (pin "D2") (pinfunction "D2_D2") (pintype "bidirectional"))
      (node (ref "X13") (pin "2") (pinfunction "1_2") (pintype "passive"))
    )
    (net (code "58") (name "Net-(X14B-1)") (class "Default")
      (node (ref "J14") (pin "3") (pinfunction "3_3") (pintype "passive"))
      (node (ref "R3") (pin "1") (pinfunction "1_1") (pintype "passive"))
      (node (ref "U$4") (pin "D3") (pinfunction "D3_D3") (pintype "bidirectional"))
      (node (ref "X14") (pin "2") (pinfunction "1_2") (pintype "passive"))
    )
    (net (code "59") (name "Net-(X14C-1)") (class "Default")
      (node (ref "C10") (pin "1") (pinfunction "1_1") (pintype "passive"))
      (node (ref "J14") (pin "5") (pinfunction "5_5") (pintype "passive"))
      (node (ref "R2") (pin "2") (pinfunction "2_2") (pintype "passive"))
      (node (ref "U$4") (pin "A2") (pinfunction "A2_A2") (pintype "bidirectional"))
      (node (ref "X14") (pin "3") (pinfunction "1_3") (pintype "passive"))
    )
    (net (code "60") (name "Net-(X15B-1)") (class "Default")
      (node (ref "J6") (pin "2") (pinfunction "2_2") (pintype "passive"))
      (node (ref "X15") (pin "2") (pinfunction "1_2") (pintype "passive"))
      (node (ref "X15") (pin "4") (pinfunction "1_4") (pintype "passive"))
    )
    (net (code "61") (name "unconnected-(J1-Pad2)") (class "Default")
      (node (ref "J1") (pin "2") (pinfunction "2_2") (pintype "passive"))
    )
    (net (code "62") (name "unconnected-(J1-Pad3)") (class "Default")
      (node (ref "J1") (pin "3") (pinfunction "3_3") (pintype "passive"))
    )
    (net (code "63") (name "unconnected-(J1-Pad4)") (class "Default")
      (node (ref "J1") (pin "4") (pinfunction "4_4") (pintype "passive"))
    )
    (net (code "64") (name "unconnected-(J1-Pad5)") (class "Default")
      (node (ref "J1") (pin "5") (pinfunction "5_5") (pintype "passive"))
    )
    (net (code "65") (name "unconnected-(J2-Pad1)") (class "Default")
      (node (ref "J2") (pin "1") (pinfunction "1_1") (pintype "passive"))
    )
    (net (code "66") (name "unconnected-(J2-Pad2)") (class "Default")
      (node (ref "J2") (pin "2") (pinfunction "2_2") (pintype "passive"))
    )
    (net (code "67") (name "unconnected-(J2-Pad3)") (class "Default")
      (node (ref "J2") (pin "3") (pinfunction "3_3") (pintype "passive"))
    )
    (net (code "68") (name "unconnected-(J2-Pad4)") (class "Default")
      (node (ref "J2") (pin "4") (pinfunction "4_4") (pintype "passive"))
    )
    (net (code "69") (name "unconnected-(J2-Pad5)") (class "Default")
      (node (ref "J2") (pin "5") (pinfunction "5_5") (pintype "passive"))
    )
    (net (code "70") (name "unconnected-(J2-Pad6)") (class "Default")
      (node (ref "J2") (pin "6") (pinfunction "6_6") (pintype "passive"))
    )
    (net (code "71") (name "unconnected-(J2-Pad7)") (class "Default")
      (node (ref "J2") (pin "7") (pinfunction "7_7") (pintype "passive"))
    )
    (net (code "72") (name "unconnected-(J2-Pad8)") (class "Default")
      (node (ref "J2") (pin "8") (pinfunction "8_8") (pintype "passive"))
    )
    (net (code "73") (name "unconnected-(J5-Pad3)") (class "Default")
      (node (ref "J5") (pin "3") (pinfunction "3_3") (pintype "passive"))
    )
    (net (code "74") (name "unconnected-(J7-Pad2)") (class "Default")
      (node (ref "J7") (pin "2") (pinfunction "2_2") (pintype "passive"))
    )
    (net (code "75") (name "unconnected-(J7-Pad3)") (class "Default")
      (node (ref "J7") (pin "3") (pinfunction "3_3") (pintype "passive"))
    )
    (net (code "76") (name "unconnected-(J13-Pad1)") (class "Default")
      (node (ref "J13") (pin "1") (pinfunction "1_1") (pintype "passive"))
    )
    (net (code "77") (name "unconnected-(J13-Pad2)") (class "Default")
      (node (ref "J13") (pin "2") (pinfunction "2_2") (pintype "passive"))
    )
    (net (code "78") (name "unconnected-(J13-Pad5)") (class "Default")
      (node (ref "J13") (pin "5") (pinfunction "5_5") (pintype "passive"))
    )
    (net (code "79") (name "unconnected-(J13-Pad6)") (class "Default")
      (node (ref "J13") (pin "6") (pinfunction "6_6") (pintype "passive"))
    )
    (net (code "80") (name "unconnected-(J14-Pad1)") (class "Default")
      (node (ref "J14") (pin "1") (pinfunction "1_1") (pintype "passive"))
    )
    (net (code "81") (name "unconnected-(J14-Pad6)") (class "Default")
      (node (ref "J14") (pin "6") (pinfunction "6_6") (pintype "passive"))
    )
    (net (code "82") (name "unconnected-(J19-Pad2)") (class "Default")
      (node (ref "J19") (pin "2") (pinfunction "2_2") (pintype "passive"))
    )
    (net (code "83") (name "unconnected-(J19-Pad3)") (class "Default")
      (node (ref "J19") (pin "3") (pinfunction "3_3") (pintype "passive"))
    )
    (net (code "84") (name "unconnected-(J19-Pad4)") (class "Default")
      (node (ref "J19") (pin "4") (pinfunction "4_4") (pintype "passive"))
    )
    (net (code "85") (name "unconnected-(J19-Pad5)") (class "Default")
      (node (ref "J19") (pin "5") (pinfunction "5_5") (pintype "passive"))
    )
    (net (code "86") (name "unconnected-(J20-Pad1)") (class "Default")
      (node (ref "J20") (pin "1") (pinfunction "1_1") (pintype "passive"))
    )
    (net (code "87") (name "unconnected-(J20-Pad2)") (class "Default")
      (node (ref "J20") (pin "2") (pinfunction "2_2") (pintype "passive"))
    )
    (net (code "88") (name "unconnected-(J20-Pad3)") (class "Default")
      (node (ref "J20") (pin "3") (pinfunction "3_3") (pintype "passive"))
    )
    (net (code "89") (name "unconnected-(J20-Pad4)") (class "Default")
      (node (ref "J20") (pin "4") (pinfunction "4_4") (pintype "passive"))
    )
    (net (code "90") (name "unconnected-(J20-Pad5)") (class "Default")
      (node (ref "J20") (pin "5") (pinfunction "5_5") (pintype "passive"))
    )
    (net (code "91") (name "unconnected-(J20-Pad6)") (class "Default")
      (node (ref "J20") (pin "6") (pinfunction "6_6") (pintype "passive"))
    )
    (net (code "92") (name "unconnected-(J20-Pad7)") (class "Default")
      (node (ref "J20") (pin "7") (pinfunction "7_7") (pintype "passive"))
    )
    (net (code "93") (name "unconnected-(J20-Pad8)") (class "Default")
      (node (ref "J20") (pin "8") (pinfunction "8_8") (pintype "passive"))
    )
    (net (code "94") (name "unconnected-(PAD1-P-Pad1)") (class "Default")
      (node (ref "PAD1") (pin "1") (pinfunction "P_1") (pintype "passive"))
    )
    (net (code "95") (name "unconnected-(PAD3-P-Pad1)") (class "Default")
      (node (ref "PAD3") (pin "1") (pinfunction "P_1") (pintype "passive"))
    )
    (net (code "96") (name "unconnected-(PAD5-P-Pad1)") (class "Default")
      (node (ref "PAD5") (pin "1") (pinfunction "P_1") (pintype "passive"))
    )
    (net (code "97") (name "unconnected-(PADANT2-P-Pad1)") (class "Default")
      (node (ref "PADANT2") (pin "1") (pinfunction "P_1") (pintype "passive"))
    )
    (net (code "98") (name "unconnected-(PADMIS1-P-Pad1)") (class "Default")
      (node (ref "PADMIS1") (pin "1") (pinfunction "P_1") (pintype "passive"))
    )
    (net (code "99") (name "unconnected-(PADMOS1-P-Pad1)") (class "Default")
      (node (ref "PADMOS1") (pin "1") (pinfunction "P_1") (pintype "passive"))
    )
    (net (code "100") (name "unconnected-(PADNSS1-P-Pad1)") (class "Default")
      (node (ref "PADNSS1") (pin "1") (pinfunction "P_1") (pintype "passive"))
    )
    (net (code "101") (name "unconnected-(PADNSS2-P-Pad1)") (class "Default")
      (node (ref "PADNSS2") (pin "1") (pinfunction "P_1") (pintype "passive"))
    )
    (net (code "102") (name "unconnected-(PADRST1-P-Pad1)") (class "Default")
      (node (ref "PADRST1") (pin "1") (pinfunction "P_1") (pintype "passive"))
    )
    (net (code "103") (name "unconnected-(PADSUP1-P-Pad1)") (class "Default")
      (node (ref "PADSUP1") (pin "1") (pinfunction "P_1") (pintype "passive"))
    )
    (net (code "104") (name "unconnected-(Q1-S-Pad2)") (class "Default")
      (node (ref "Q1") (pin "2") (pinfunction "S_2") (pintype "passive"))
    )
    (net (code "105") (name "unconnected-(U$4-Pad3.3V)") (class "Default")
      (node (ref "U$4") (pin "3.3V") (pinfunction "3.3V_3.3V") (pintype "bidirectional"))
    )
    (net (code "106") (name "unconnected-(U$4-PadAREF)") (class "Default")
      (node (ref "U$4") (pin "AREF") (pinfunction "AREF_AREF") (pintype "bidirectional"))
    )
    (net (code "107") (name "unconnected-(U$4-PadD9)") (class "Default")
      (node (ref "U$4") (pin "D9") (pinfunction "D9_D9") (pintype "bidirectional"))
    )
    (net (code "108") (name "unconnected-(U$4-PadICSP3)") (class "Default")
      (node (ref "U$4") (pin "ICSP3") (pinfunction "ICSP3_ICSP3") (pintype "bidirectional"))
    )
    (net (code "109") (name "unconnected-(U$4-PadICSP4)") (class "Default")
      (node (ref "U$4") (pin "ICSP4") (pinfunction "ICSP4_ICSP4") (pintype "bidirectional"))
    )
    (net (code "110") (name "unconnected-(U$4-PadICSP5)") (class "Default")
      (node (ref "U$4") (pin "ICSP5") (pinfunction "ICSP5_ICSP5") (pintype "bidirectional"))
    )
    (net (code "111") (name "unconnected-(U$4-PadICSP6)") (class "Default")
      (node (ref "U$4") (pin "ICSP6") (pinfunction "ICSP6_ICSP6") (pintype "bidirectional"))
    )
    (net (code "112") (name "unconnected-(U$4-PadRST1)") (class "Default")
      (node (ref "U$4") (pin "RST1") (pinfunction "RST1_RST1") (pintype "bidirectional"))
    )
  )
)
